# 22-1G_SFP.net
KiCad netlist of a schematic drawn in Altium Designer
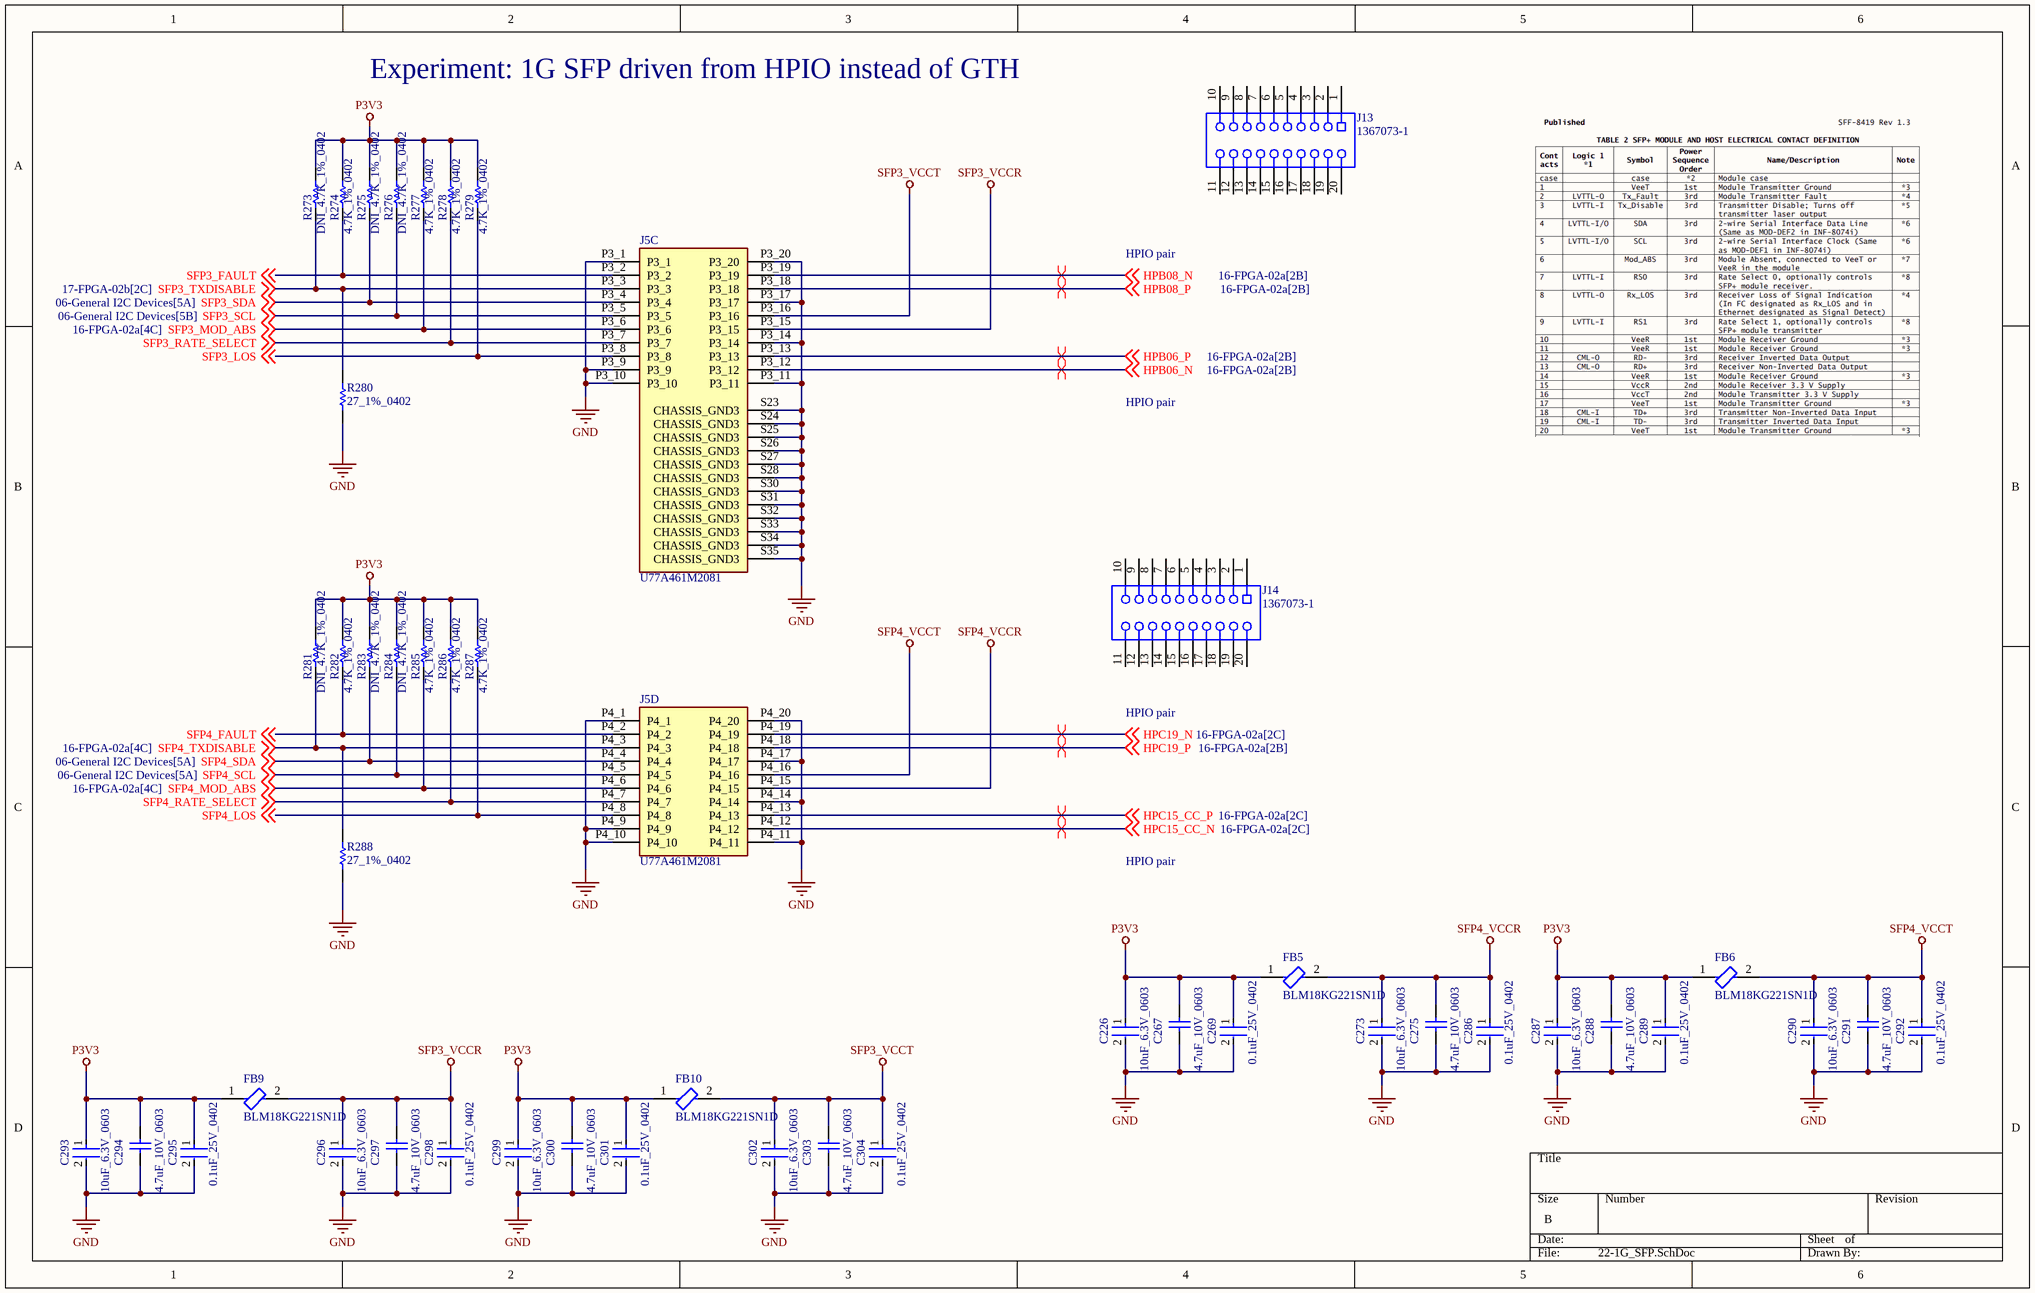
[diagram p0: 22-1G_SFP.SchDoc]

(export (version "E")
  (design (tool "Eeschema 10.0.6"))
  (components
    (comp (ref "C226")
      (value "10uF_6.3V_0603")
      (footprint "FP-C0603C106M9PACTU-MFG")
      (description "CAP CER 10UF 6.3V X5R 0603")
      (fields
        (field (name "MANUFACTURER PART NUMBER") "C0603C106M9PACTU")
        (field (name "MANUFACTURER") "Kemet")
      )
      (libsource (lib "Altium Content Vault") (part "b4654b650e69147ec39a6b967a45e02"))
    )
    (comp (ref "C267")
      (value "4.7uF_10V_0603")
      (footprint "CAPC1608X87X35NL15T15")
      (fields (field (name "PART NUMBER") "C0603C475K8PACTU") (field (name "MANUFACTURER") "Kemet"))
      (libsource (lib "Altium Content Vault") (part "CAP"))
    )
    (comp (ref "C269")
      (value "0.1uF_25V_0402")
      (footprint "FP-0402-L_1_0_1-W_0_5_0_1-IPC_C")
      (description "General Purpose Ceramic Capacitor, 0402, 100nF, 10%, X7R, 15%, 25V")
      (fields (field (name "VOLTAGE") "25V") (field (name "TOLERANCE") "10%"))
      (libsource (lib "Altium Content Vault") (part "b4654b650e69147ec39a6b967a45e02"))
    )
    (comp (ref "C273")
      (value "10uF_6.3V_0603")
      (footprint "FP-C0603C106M9PACTU-MFG")
      (description "CAP CER 10UF 6.3V X5R 0603")
      (fields
        (field (name "MANUFACTURER PART NUMBER") "C0603C106M9PACTU")
        (field (name "MANUFACTURER") "Kemet")
      )
      (libsource (lib "Altium Content Vault") (part "b4654b650e69147ec39a6b967a45e02"))
    )
    (comp (ref "C275")
      (value "4.7uF_10V_0603")
      (footprint "CAPC1608X87X35NL15T15")
      (fields (field (name "PART NUMBER") "C0603C475K8PACTU") (field (name "MANUFACTURER") "Kemet"))
      (libsource (lib "Altium Content Vault") (part "CAP"))
    )
    (comp (ref "C286")
      (value "0.1uF_25V_0402")
      (footprint "FP-0402-L_1_0_1-W_0_5_0_1-IPC_C")
      (description "General Purpose Ceramic Capacitor, 0402, 100nF, 10%, X7R, 15%, 25V")
      (fields (field (name "VOLTAGE") "25V") (field (name "TOLERANCE") "10%"))
      (libsource (lib "Altium Content Vault") (part "b4654b650e69147ec39a6b967a45e02"))
    )
    (comp (ref "C287")
      (value "10uF_6.3V_0603")
      (footprint "FP-C0603C106M9PACTU-MFG")
      (description "CAP CER 10UF 6.3V X5R 0603")
      (fields
        (field (name "MANUFACTURER PART NUMBER") "C0603C106M9PACTU")
        (field (name "MANUFACTURER") "Kemet")
      )
      (libsource (lib "Altium Content Vault") (part "b4654b650e69147ec39a6b967a45e02"))
    )
    (comp (ref "C288")
      (value "4.7uF_10V_0603")
      (footprint "CAPC1608X87X35NL15T15")
      (fields (field (name "PART NUMBER") "C0603C475K8PACTU") (field (name "MANUFACTURER") "Kemet"))
      (libsource (lib "Altium Content Vault") (part "CAP"))
    )
    (comp (ref "C289")
      (value "0.1uF_25V_0402")
      (footprint "FP-0402-L_1_0_1-W_0_5_0_1-IPC_C")
      (description "General Purpose Ceramic Capacitor, 0402, 100nF, 10%, X7R, 15%, 25V")
      (fields (field (name "VOLTAGE") "25V") (field (name "TOLERANCE") "10%"))
      (libsource (lib "Altium Content Vault") (part "b4654b650e69147ec39a6b967a45e02"))
    )
    (comp (ref "C290")
      (value "10uF_6.3V_0603")
      (footprint "FP-C0603C106M9PACTU-MFG")
      (description "CAP CER 10UF 6.3V X5R 0603")
      (fields
        (field (name "MANUFACTURER PART NUMBER") "C0603C106M9PACTU")
        (field (name "MANUFACTURER") "Kemet")
      )
      (libsource (lib "Altium Content Vault") (part "b4654b650e69147ec39a6b967a45e02"))
    )
    (comp (ref "C291")
      (value "4.7uF_10V_0603")
      (footprint "CAPC1608X87X35NL15T15")
      (fields (field (name "PART NUMBER") "C0603C475K8PACTU") (field (name "MANUFACTURER") "Kemet"))
      (libsource (lib "Altium Content Vault") (part "CAP"))
    )
    (comp (ref "C292")
      (value "0.1uF_25V_0402")
      (footprint "FP-0402-L_1_0_1-W_0_5_0_1-IPC_C")
      (description "General Purpose Ceramic Capacitor, 0402, 100nF, 10%, X7R, 15%, 25V")
      (fields (field (name "VOLTAGE") "25V") (field (name "TOLERANCE") "10%"))
      (libsource (lib "Altium Content Vault") (part "b4654b650e69147ec39a6b967a45e02"))
    )
    (comp (ref "C293")
      (value "10uF_6.3V_0603")
      (footprint "FP-C0603C106M9PACTU-MFG")
      (description "CAP CER 10UF 6.3V X5R 0603")
      (fields
        (field (name "MANUFACTURER PART NUMBER") "C0603C106M9PACTU")
        (field (name "MANUFACTURER") "Kemet")
      )
      (libsource (lib "Altium Content Vault") (part "b4654b650e69147ec39a6b967a45e02"))
    )
    (comp (ref "C294")
      (value "4.7uF_10V_0603")
      (footprint "CAPC1608X87X35NL15T15")
      (fields (field (name "PART NUMBER") "C0603C475K8PACTU") (field (name "MANUFACTURER") "Kemet"))
      (libsource (lib "Altium Content Vault") (part "CAP"))
    )
    (comp (ref "C295")
      (value "0.1uF_25V_0402")
      (footprint "FP-0402-L_1_0_1-W_0_5_0_1-IPC_C")
      (description "General Purpose Ceramic Capacitor, 0402, 100nF, 10%, X7R, 15%, 25V")
      (fields (field (name "VOLTAGE") "25V") (field (name "TOLERANCE") "10%"))
      (libsource (lib "Altium Content Vault") (part "b4654b650e69147ec39a6b967a45e02"))
    )
    (comp (ref "C296")
      (value "10uF_6.3V_0603")
      (footprint "FP-C0603C106M9PACTU-MFG")
      (description "CAP CER 10UF 6.3V X5R 0603")
      (fields
        (field (name "MANUFACTURER PART NUMBER") "C0603C106M9PACTU")
        (field (name "MANUFACTURER") "Kemet")
      )
      (libsource (lib "Altium Content Vault") (part "b4654b650e69147ec39a6b967a45e02"))
    )
    (comp (ref "C297")
      (value "4.7uF_10V_0603")
      (footprint "CAPC1608X87X35NL15T15")
      (fields (field (name "PART NUMBER") "C0603C475K8PACTU") (field (name "MANUFACTURER") "Kemet"))
      (libsource (lib "Altium Content Vault") (part "CAP"))
    )
    (comp (ref "C298")
      (value "0.1uF_25V_0402")
      (footprint "FP-0402-L_1_0_1-W_0_5_0_1-IPC_C")
      (description "General Purpose Ceramic Capacitor, 0402, 100nF, 10%, X7R, 15%, 25V")
      (fields (field (name "VOLTAGE") "25V") (field (name "TOLERANCE") "10%"))
      (libsource (lib "Altium Content Vault") (part "b4654b650e69147ec39a6b967a45e02"))
    )
    (comp (ref "C299")
      (value "10uF_6.3V_0603")
      (footprint "FP-C0603C106M9PACTU-MFG")
      (description "CAP CER 10UF 6.3V X5R 0603")
      (fields
        (field (name "MANUFACTURER PART NUMBER") "C0603C106M9PACTU")
        (field (name "MANUFACTURER") "Kemet")
      )
      (libsource (lib "Altium Content Vault") (part "b4654b650e69147ec39a6b967a45e02"))
    )
    (comp (ref "C300")
      (value "4.7uF_10V_0603")
      (footprint "CAPC1608X87X35NL15T15")
      (fields (field (name "PART NUMBER") "C0603C475K8PACTU") (field (name "MANUFACTURER") "Kemet"))
      (libsource (lib "Altium Content Vault") (part "CAP"))
    )
    (comp (ref "C301")
      (value "0.1uF_25V_0402")
      (footprint "FP-0402-L_1_0_1-W_0_5_0_1-IPC_C")
      (description "General Purpose Ceramic Capacitor, 0402, 100nF, 10%, X7R, 15%, 25V")
      (fields (field (name "VOLTAGE") "25V") (field (name "TOLERANCE") "10%"))
      (libsource (lib "Altium Content Vault") (part "b4654b650e69147ec39a6b967a45e02"))
    )
    (comp (ref "C302")
      (value "10uF_6.3V_0603")
      (footprint "FP-C0603C106M9PACTU-MFG")
      (description "CAP CER 10UF 6.3V X5R 0603")
      (fields
        (field (name "MANUFACTURER PART NUMBER") "C0603C106M9PACTU")
        (field (name "MANUFACTURER") "Kemet")
      )
      (libsource (lib "Altium Content Vault") (part "b4654b650e69147ec39a6b967a45e02"))
    )
    (comp (ref "C303")
      (value "4.7uF_10V_0603")
      (footprint "CAPC1608X87X35NL15T15")
      (fields (field (name "PART NUMBER") "C0603C475K8PACTU") (field (name "MANUFACTURER") "Kemet"))
      (libsource (lib "Altium Content Vault") (part "CAP"))
    )
    (comp (ref "C304")
      (value "0.1uF_25V_0402")
      (footprint "FP-0402-L_1_0_1-W_0_5_0_1-IPC_C")
      (description "General Purpose Ceramic Capacitor, 0402, 100nF, 10%, X7R, 15%, 25V")
      (fields (field (name "VOLTAGE") "25V") (field (name "TOLERANCE") "10%"))
      (libsource (lib "Altium Content Vault") (part "b4654b650e69147ec39a6b967a45e02"))
    )
    (comp (ref "FB5")
      (value "BLM18KG221SN1D")
      (footprint "FP-BLM18-0_15-t0_8-IPC_B")
      (description "Chip Ferrite Bead, 0603, 220Ω @ 100MHz, 0.05Ω, 25%, 2.2A")
      (fields (field (name "TOLERANCE") "25%"))
      (libsource (lib "Altium Content Vault") (part "5f30dd21d616792df468990f7003faa"))
    )
    (comp (ref "FB6")
      (value "BLM18KG221SN1D")
      (footprint "FP-BLM18-0_15-t0_8-IPC_B")
      (description "Chip Ferrite Bead, 0603, 220Ω @ 100MHz, 0.05Ω, 25%, 2.2A")
      (fields (field (name "TOLERANCE") "25%"))
      (libsource (lib "Altium Content Vault") (part "5f30dd21d616792df468990f7003faa"))
    )
    (comp (ref "FB9")
      (value "BLM18KG221SN1D")
      (footprint "FP-BLM18-0_15-t0_8-IPC_B")
      (description "Chip Ferrite Bead, 0603, 220Ω @ 100MHz, 0.05Ω, 25%, 2.2A")
      (fields (field (name "TOLERANCE") "25%"))
      (libsource (lib "Altium Content Vault") (part "5f30dd21d616792df468990f7003faa"))
    )
    (comp (ref "FB10")
      (value "BLM18KG221SN1D")
      (footprint "FP-BLM18-0_15-t0_8-IPC_B")
      (description "Chip Ferrite Bead, 0603, 220Ω @ 100MHz, 0.05Ω, 25%, 2.2A")
      (fields (field (name "TOLERANCE") "25%"))
      (libsource (lib "Altium Content Vault") (part "5f30dd21d616792df468990f7003faa"))
    )
    (comp (ref "J5")
      (value "U77A461M2081")
      (footprint "AMPHENOL_U77A461M2081")
      (fields (field (name "MF") "AMPHENOL ICC / FCI"))
      (libsource (lib "U77A461M2081") (part "U77A461M2081"))
    )
    (comp (ref "J13")
      (value "1367073-1")
      (footprint "TECO-1367073-1_V")
      (fields (field (name "MANUFACTURER") "TE Connectivity"))
      (libsource (lib "Altium Content Vault") (part "CN-2P-F-R20_B"))
    )
    (comp (ref "J14")
      (value "1367073-1")
      (footprint "TECO-1367073-1_V")
      (fields (field (name "MANUFACTURER") "TE Connectivity"))
      (libsource (lib "Altium Content Vault") (part "CN-2P-F-R20_B"))
    )
    (comp (ref "R273")
      (value "DNI_4.7K_1%_0402")
      (footprint "RESC1005X40X25NL10T10")
      (fields (field (name "MANUFACTURER") "Bourns") (field (name "PART NUMBER") "CR0402-FX-4701GLF"))
      (libsource (lib "Altium Content Vault") (part "RES"))
    )
    (comp (ref "R274")
      (value "4.7K_1%_0402")
      (footprint "RESC1005X40X25NL10T10")
      (fields (field (name "MANUFACTURER") "Bourns") (field (name "PART NUMBER") "CR0402-FX-4701GLF"))
      (libsource (lib "Altium Content Vault") (part "RES"))
    )
    (comp (ref "R275")
      (value "DNI_4.7K_1%_0402")
      (footprint "RESC1005X40X25NL10T10")
      (fields (field (name "MANUFACTURER") "Bourns") (field (name "PART NUMBER") "CR0402-FX-4701GLF"))
      (libsource (lib "Altium Content Vault") (part "RES"))
    )
    (comp (ref "R276")
      (value "DNI_4.7K_1%_0402")
      (footprint "RESC1005X40X25NL10T10")
      (fields (field (name "MANUFACTURER") "Bourns") (field (name "PART NUMBER") "CR0402-FX-4701GLF"))
      (libsource (lib "Altium Content Vault") (part "RES"))
    )
    (comp (ref "R277")
      (value "4.7K_1%_0402")
      (footprint "RESC1005X40X25NL10T10")
      (fields (field (name "MANUFACTURER") "Bourns") (field (name "PART NUMBER") "CR0402-FX-4701GLF"))
      (libsource (lib "Altium Content Vault") (part "RES"))
    )
    (comp (ref "R278")
      (value "4.7K_1%_0402")
      (footprint "RESC1005X40X25NL10T10")
      (fields (field (name "MANUFACTURER") "Bourns") (field (name "PART NUMBER") "CR0402-FX-4701GLF"))
      (libsource (lib "Altium Content Vault") (part "RES"))
    )
    (comp (ref "R279")
      (value "4.7K_1%_0402")
      (footprint "RESC1005X40X25NL10T10")
      (fields (field (name "MANUFACTURER") "Bourns") (field (name "PART NUMBER") "CR0402-FX-4701GLF"))
      (libsource (lib "Altium Content Vault") (part "RES"))
    )
    (comp (ref "R280")
      (value "27_1%_0402")
      (footprint "RESC1005X40X25NL05T05")
      (fields (field (name "PART NUMBER") "CRCW040227R0FKED") (field (name "MANUFACTURER") "Vishay Dale"))
      (libsource (lib "Altium Content Vault") (part "RES"))
    )
    (comp (ref "R281")
      (value "DNI_4.7K_1%_0402")
      (footprint "RESC1005X40X25NL10T10")
      (fields (field (name "MANUFACTURER") "Bourns") (field (name "PART NUMBER") "CR0402-FX-4701GLF"))
      (libsource (lib "Altium Content Vault") (part "RES"))
    )
    (comp (ref "R282")
      (value "4.7K_1%_0402")
      (footprint "RESC1005X40X25NL10T10")
      (fields (field (name "MANUFACTURER") "Bourns") (field (name "PART NUMBER") "CR0402-FX-4701GLF"))
      (libsource (lib "Altium Content Vault") (part "RES"))
    )
    (comp (ref "R283")
      (value "DNI_4.7K_1%_0402")
      (footprint "RESC1005X40X25NL10T10")
      (fields (field (name "MANUFACTURER") "Bourns") (field (name "PART NUMBER") "CR0402-FX-4701GLF"))
      (libsource (lib "Altium Content Vault") (part "RES"))
    )
    (comp (ref "R284")
      (value "DNI_4.7K_1%_0402")
      (footprint "RESC1005X40X25NL10T10")
      (fields (field (name "MANUFACTURER") "Bourns") (field (name "PART NUMBER") "CR0402-FX-4701GLF"))
      (libsource (lib "Altium Content Vault") (part "RES"))
    )
    (comp (ref "R285")
      (value "4.7K_1%_0402")
      (footprint "RESC1005X40X25NL10T10")
      (fields (field (name "MANUFACTURER") "Bourns") (field (name "PART NUMBER") "CR0402-FX-4701GLF"))
      (libsource (lib "Altium Content Vault") (part "RES"))
    )
    (comp (ref "R286")
      (value "4.7K_1%_0402")
      (footprint "RESC1005X40X25NL10T10")
      (fields (field (name "MANUFACTURER") "Bourns") (field (name "PART NUMBER") "CR0402-FX-4701GLF"))
      (libsource (lib "Altium Content Vault") (part "RES"))
    )
    (comp (ref "R287")
      (value "4.7K_1%_0402")
      (footprint "RESC1005X40X25NL10T10")
      (fields (field (name "MANUFACTURER") "Bourns") (field (name "PART NUMBER") "CR0402-FX-4701GLF"))
      (libsource (lib "Altium Content Vault") (part "RES"))
    )
    (comp (ref "R288")
      (value "27_1%_0402")
      (footprint "RESC1005X40X25NL05T05")
      (fields (field (name "PART NUMBER") "CRCW040227R0FKED") (field (name "MANUFACTURER") "Vishay Dale"))
      (libsource (lib "Altium Content Vault") (part "RES"))
    )
  )
  (nets
    (net (code "1") (name "GND") (class "Default")
      (node (ref "C226") (pin "2") (pinfunction "2_2") (pintype "passive"))
      (node (ref "C267") (pin "1") (pinfunction "1_1") (pintype "passive"))
      (node (ref "C269") (pin "2") (pinfunction "2_2") (pintype "passive"))
      (node (ref "C273") (pin "2") (pinfunction "2_2") (pintype "passive"))
      (node (ref "C275") (pin "1") (pinfunction "1_1") (pintype "passive"))
      (node (ref "C286") (pin "2") (pinfunction "2_2") (pintype "passive"))
      (node (ref "C287") (pin "2") (pinfunction "2_2") (pintype "passive"))
      (node (ref "C288") (pin "1") (pinfunction "1_1") (pintype "passive"))
      (node (ref "C289") (pin "2") (pinfunction "2_2") (pintype "passive"))
      (node (ref "C290") (pin "2") (pinfunction "2_2") (pintype "passive"))
      (node (ref "C291") (pin "1") (pinfunction "1_1") (pintype "passive"))
      (node (ref "C292") (pin "2") (pinfunction "2_2") (pintype "passive"))
      (node (ref "C293") (pin "2") (pinfunction "2_2") (pintype "passive"))
      (node (ref "C294") (pin "1") (pinfunction "1_1") (pintype "passive"))
      (node (ref "C295") (pin "2") (pinfunction "2_2") (pintype "passive"))
      (node (ref "C296") (pin "2") (pinfunction "2_2") (pintype "passive"))
      (node (ref "C297") (pin "1") (pinfunction "1_1") (pintype "passive"))
      (node (ref "C298") (pin "2") (pinfunction "2_2") (pintype "passive"))
      (node (ref "C299") (pin "2") (pinfunction "2_2") (pintype "passive"))
      (node (ref "C300") (pin "1") (pinfunction "1_1") (pintype "passive"))
      (node (ref "C301") (pin "2") (pinfunction "2_2") (pintype "passive"))
      (node (ref "C302") (pin "2") (pinfunction "2_2") (pintype "passive"))
      (node (ref "C303") (pin "1") (pinfunction "1_1") (pintype "passive"))
      (node (ref "C304") (pin "2") (pinfunction "2_2") (pintype "passive"))
      (node (ref "J5") (pin "P3_1") (pinfunction "P3_1_P3_1") (pintype "passive"))
      (node (ref "J5") (pin "P3_10") (pinfunction "P3_10_P3_10") (pintype "passive"))
      (node (ref "J5") (pin "P3_11") (pinfunction "P3_11_P3_11") (pintype "passive"))
      (node (ref "J5") (pin "P3_14") (pinfunction "P3_14_P3_14") (pintype "passive"))
      (node (ref "J5") (pin "P3_17") (pinfunction "P3_17_P3_17") (pintype "passive"))
      (node (ref "J5") (pin "P3_20") (pinfunction "P3_20_P3_20") (pintype "passive"))
      (node (ref "J5") (pin "P3_9") (pinfunction "P3_9_P3_9") (pintype "passive"))
      (node (ref "J5") (pin "P4_1") (pinfunction "P4_1_P4_1") (pintype "passive"))
      (node (ref "J5") (pin "P4_10") (pinfunction "P4_10_P4_10") (pintype "passive"))
      (node (ref "J5") (pin "P4_11") (pinfunction "P4_11_P4_11") (pintype "passive"))
      (node (ref "J5") (pin "P4_14") (pinfunction "P4_14_P4_14") (pintype "passive"))
      (node (ref "J5") (pin "P4_17") (pinfunction "P4_17_P4_17") (pintype "passive"))
      (node (ref "J5") (pin "P4_20") (pinfunction "P4_20_P4_20") (pintype "passive"))
      (node (ref "J5") (pin "P4_9") (pinfunction "P4_9_P4_9") (pintype "passive"))
      (node (ref "J5") (pin "S23") (pinfunction "CHASSIS_GND3_S23") (pintype "passive"))
      (node (ref "J5") (pin "S24") (pinfunction "CHASSIS_GND3_S24") (pintype "passive"))
      (node (ref "J5") (pin "S25") (pinfunction "CHASSIS_GND3_S25") (pintype "passive"))
      (node (ref "J5") (pin "S26") (pinfunction "CHASSIS_GND3_S26") (pintype "passive"))
      (node (ref "J5") (pin "S27") (pinfunction "CHASSIS_GND3_S27") (pintype "passive"))
      (node (ref "J5") (pin "S28") (pinfunction "CHASSIS_GND3_S28") (pintype "passive"))
      (node (ref "J5") (pin "S30") (pinfunction "CHASSIS_GND3_S30") (pintype "passive"))
      (node (ref "J5") (pin "S31") (pinfunction "CHASSIS_GND3_S31") (pintype "passive"))
      (node (ref "J5") (pin "S32") (pinfunction "CHASSIS_GND3_S32") (pintype "passive"))
      (node (ref "J5") (pin "S33") (pinfunction "CHASSIS_GND3_S33") (pintype "passive"))
      (node (ref "J5") (pin "S34") (pinfunction "CHASSIS_GND3_S34") (pintype "passive"))
      (node (ref "J5") (pin "S35") (pinfunction "CHASSIS_GND3_S35") (pintype "passive"))
      (node (ref "R280") (pin "1") (pinfunction "1_1") (pintype "passive"))
      (node (ref "R288") (pin "1") (pinfunction "1_1") (pintype "passive"))
    )
    (net (code "2") (name "HPB06_N") (class "Default")
      (node (ref "J5") (pin "P3_12") (pinfunction "P3_12_P3_12") (pintype "passive"))
    )
    (net (code "3") (name "HPB06_P") (class "Default")
      (node (ref "J5") (pin "P3_13") (pinfunction "P3_13_P3_13") (pintype "passive"))
    )
    (net (code "4") (name "HPB08_N") (class "Default")
      (node (ref "J5") (pin "P3_19") (pinfunction "P3_19_P3_19") (pintype "passive"))
    )
    (net (code "5") (name "HPB08_P") (class "Default")
      (node (ref "J5") (pin "P3_18") (pinfunction "P3_18_P3_18") (pintype "passive"))
    )
    (net (code "6") (name "HPC15_CC_N") (class "Default")
      (node (ref "J5") (pin "P4_12") (pinfunction "P4_12_P4_12") (pintype "passive"))
    )
    (net (code "7") (name "HPC15_CC_P") (class "Default")
      (node (ref "J5") (pin "P4_13") (pinfunction "P4_13_P4_13") (pintype "passive"))
    )
    (net (code "8") (name "HPC19_N") (class "Default")
      (node (ref "J5") (pin "P4_19") (pinfunction "P4_19_P4_19") (pintype "passive"))
    )
    (net (code "9") (name "HPC19_P") (class "Default")
      (node (ref "J5") (pin "P4_18") (pinfunction "P4_18_P4_18") (pintype "passive"))
    )
    (net (code "10") (name "P3V3") (class "Default")
      (node (ref "C226") (pin "1") (pinfunction "1_1") (pintype "passive"))
      (node (ref "C267") (pin "2") (pinfunction "2_2") (pintype "passive"))
      (node (ref "C269") (pin "1") (pinfunction "1_1") (pintype "passive"))
      (node (ref "C287") (pin "1") (pinfunction "1_1") (pintype "passive"))
      (node (ref "C288") (pin "2") (pinfunction "2_2") (pintype "passive"))
      (node (ref "C289") (pin "1") (pinfunction "1_1") (pintype "passive"))
      (node (ref "C293") (pin "1") (pinfunction "1_1") (pintype "passive"))
      (node (ref "C294") (pin "2") (pinfunction "2_2") (pintype "passive"))
      (node (ref "C295") (pin "1") (pinfunction "1_1") (pintype "passive"))
      (node (ref "C299") (pin "1") (pinfunction "1_1") (pintype "passive"))
      (node (ref "C300") (pin "2") (pinfunction "2_2") (pintype "passive"))
      (node (ref "C301") (pin "1") (pinfunction "1_1") (pintype "passive"))
      (node (ref "FB10") (pin "1") (pinfunction "1_1") (pintype "passive"))
      (node (ref "FB5") (pin "1") (pinfunction "1_1") (pintype "passive"))
      (node (ref "FB6") (pin "1") (pinfunction "1_1") (pintype "passive"))
      (node (ref "FB9") (pin "1") (pinfunction "1_1") (pintype "passive"))
      (node (ref "R273") (pin "1") (pinfunction "1_1") (pintype "passive"))
      (node (ref "R274") (pin "1") (pinfunction "1_1") (pintype "passive"))
      (node (ref "R275") (pin "1") (pinfunction "1_1") (pintype "passive"))
      (node (ref "R276") (pin "1") (pinfunction "1_1") (pintype "passive"))
      (node (ref "R277") (pin "1") (pinfunction "1_1") (pintype "passive"))
      (node (ref "R278") (pin "1") (pinfunction "1_1") (pintype "passive"))
      (node (ref "R279") (pin "1") (pinfunction "1_1") (pintype "passive"))
      (node (ref "R281") (pin "1") (pinfunction "1_1") (pintype "passive"))
      (node (ref "R282") (pin "1") (pinfunction "1_1") (pintype "passive"))
      (node (ref "R283") (pin "1") (pinfunction "1_1") (pintype "passive"))
      (node (ref "R284") (pin "1") (pinfunction "1_1") (pintype "passive"))
      (node (ref "R285") (pin "1") (pinfunction "1_1") (pintype "passive"))
      (node (ref "R286") (pin "1") (pinfunction "1_1") (pintype "passive"))
      (node (ref "R287") (pin "1") (pinfunction "1_1") (pintype "passive"))
    )
    (net (code "11") (name "SFP3_FAULT") (class "Default")
      (node (ref "J5") (pin "P3_2") (pinfunction "P3_2_P3_2") (pintype "passive"))
      (node (ref "R274") (pin "2") (pinfunction "2_2") (pintype "passive"))
    )
    (net (code "12") (name "SFP3_LOS") (class "Default")
      (node (ref "J5") (pin "P3_8") (pinfunction "P3_8_P3_8") (pintype "passive"))
      (node (ref "R279") (pin "2") (pinfunction "2_2") (pintype "passive"))
    )
    (net (code "13") (name "SFP3_MOD_ABS") (class "Default")
      (node (ref "J5") (pin "P3_6") (pinfunction "P3_6_P3_6") (pintype "passive"))
      (node (ref "R277") (pin "2") (pinfunction "2_2") (pintype "passive"))
    )
    (net (code "14") (name "SFP3_RATE_SELECT") (class "Default")
      (node (ref "J5") (pin "P3_7") (pinfunction "P3_7_P3_7") (pintype "passive"))
      (node (ref "R278") (pin "2") (pinfunction "2_2") (pintype "passive"))
    )
    (net (code "15") (name "SFP3_SCL") (class "Default")
      (node (ref "J5") (pin "P3_5") (pinfunction "P3_5_P3_5") (pintype "passive"))
      (node (ref "R276") (pin "2") (pinfunction "2_2") (pintype "passive"))
    )
    (net (code "16") (name "SFP3_SDA") (class "Default")
      (node (ref "J5") (pin "P3_4") (pinfunction "P3_4_P3_4") (pintype "passive"))
      (node (ref "R275") (pin "2") (pinfunction "2_2") (pintype "passive"))
    )
    (net (code "17") (name "SFP3_TXDISABLE") (class "Default")
      (node (ref "J5") (pin "P3_3") (pinfunction "P3_3_P3_3") (pintype "passive"))
      (node (ref "R273") (pin "2") (pinfunction "2_2") (pintype "passive"))
      (node (ref "R280") (pin "2") (pinfunction "2_2") (pintype "passive"))
    )
    (net (code "18") (name "SFP3_VCCR") (class "Default")
      (node (ref "C296") (pin "1") (pinfunction "1_1") (pintype "passive"))
      (node (ref "C297") (pin "2") (pinfunction "2_2") (pintype "passive"))
      (node (ref "C298") (pin "1") (pinfunction "1_1") (pintype "passive"))
      (node (ref "FB9") (pin "2") (pinfunction "2_2") (pintype "passive"))
      (node (ref "J5") (pin "P3_15") (pinfunction "P3_15_P3_15") (pintype "passive"))
    )
    (net (code "19") (name "SFP3_VCCT") (class "Default")
      (node (ref "C302") (pin "1") (pinfunction "1_1") (pintype "passive"))
      (node (ref "C303") (pin "2") (pinfunction "2_2") (pintype "passive"))
      (node (ref "C304") (pin "1") (pinfunction "1_1") (pintype "passive"))
      (node (ref "FB10") (pin "2") (pinfunction "2_2") (pintype "passive"))
      (node (ref "J5") (pin "P3_16") (pinfunction "P3_16_P3_16") (pintype "passive"))
    )
    (net (code "20") (name "SFP4_FAULT") (class "Default")
      (node (ref "J5") (pin "P4_2") (pinfunction "P4_2_P4_2") (pintype "passive"))
      (node (ref "R282") (pin "2") (pinfunction "2_2") (pintype "passive"))
    )
    (net (code "21") (name "SFP4_LOS") (class "Default")
      (node (ref "J5") (pin "P4_8") (pinfunction "P4_8_P4_8") (pintype "passive"))
      (node (ref "R287") (pin "2") (pinfunction "2_2") (pintype "passive"))
    )
    (net (code "22") (name "SFP4_MOD_ABS") (class "Default")
      (node (ref "J5") (pin "P4_6") (pinfunction "P4_6_P4_6") (pintype "passive"))
      (node (ref "R285") (pin "2") (pinfunction "2_2") (pintype "passive"))
    )
    (net (code "23") (name "SFP4_RATE_SELECT") (class "Default")
      (node (ref "J5") (pin "P4_7") (pinfunction "P4_7_P4_7") (pintype "passive"))
      (node (ref "R286") (pin "2") (pinfunction "2_2") (pintype "passive"))
    )
    (net (code "24") (name "SFP4_SCL") (class "Default")
      (node (ref "J5") (pin "P4_5") (pinfunction "P4_5_P4_5") (pintype "passive"))
      (node (ref "R284") (pin "2") (pinfunction "2_2") (pintype "passive"))
    )
    (net (code "25") (name "SFP4_SDA") (class "Default")
      (node (ref "J5") (pin "P4_4") (pinfunction "P4_4_P4_4") (pintype "passive"))
      (node (ref "R283") (pin "2") (pinfunction "2_2") (pintype "passive"))
    )
    (net (code "26") (name "SFP4_TXDISABLE") (class "Default")
      (node (ref "J5") (pin "P4_3") (pinfunction "P4_3_P4_3") (pintype "passive"))
      (node (ref "R281") (pin "2") (pinfunction "2_2") (pintype "passive"))
      (node (ref "R288") (pin "2") (pinfunction "2_2") (pintype "passive"))
    )
    (net (code "27") (name "SFP4_VCCR") (class "Default")
      (node (ref "C273") (pin "1") (pinfunction "1_1") (pintype "passive"))
      (node (ref "C275") (pin "2") (pinfunction "2_2") (pintype "passive"))
      (node (ref "C286") (pin "1") (pinfunction "1_1") (pintype "passive"))
      (node (ref "FB5") (pin "2") (pinfunction "2_2") (pintype "passive"))
      (node (ref "J5") (pin "P4_15") (pinfunction "P4_15_P4_15") (pintype "passive"))
    )
    (net (code "28") (name "SFP4_VCCT") (class "Default")
      (node (ref "C290") (pin "1") (pinfunction "1_1") (pintype "passive"))
      (node (ref "C291") (pin "2") (pinfunction "2_2") (pintype "passive"))
      (node (ref "C292") (pin "1") (pinfunction "1_1") (pintype "passive"))
      (node (ref "FB6") (pin "2") (pinfunction "2_2") (pintype "passive"))
      (node (ref "J5") (pin "P4_16") (pinfunction "P4_16_P4_16") (pintype "passive"))
    )
    (net (code "29") (name "unconnected-(J13-Pad1)") (class "Default")
      (node (ref "J13") (pin "1") (pinfunction "1_1") (pintype "passive"))
    )
    (net (code "30") (name "unconnected-(J13-Pad2)") (class "Default")
      (node (ref "J13") (pin "2") (pinfunction "2_2") (pintype "passive"))
    )
    (net (code "31") (name "unconnected-(J13-Pad3)") (class "Default")
      (node (ref "J13") (pin "3") (pinfunction "3_3") (pintype "passive"))
    )
    (net (code "32") (name "unconnected-(J13-Pad4)") (class "Default")
      (node (ref "J13") (pin "4") (pinfunction "4_4") (pintype "passive"))
    )
    (net (code "33") (name "unconnected-(J13-Pad5)") (class "Default")
      (node (ref "J13") (pin "5") (pinfunction "5_5") (pintype "passive"))
    )
    (net (code "34") (name "unconnected-(J13-Pad6)") (class "Default")
      (node (ref "J13") (pin "6") (pinfunction "6_6") (pintype "passive"))
    )
    (net (code "35") (name "unconnected-(J13-Pad7)") (class "Default")
      (node (ref "J13") (pin "7") (pinfunction "7_7") (pintype "passive"))
    )
    (net (code "36") (name "unconnected-(J13-Pad8)") (class "Default")
      (node (ref "J13") (pin "8") (pinfunction "8_8") (pintype "passive"))
    )
    (net (code "37") (name "unconnected-(J13-Pad9)") (class "Default")
      (node (ref "J13") (pin "9") (pinfunction "9_9") (pintype "passive"))
    )
    (net (code "38") (name "unconnected-(J13-Pad10)") (class "Default")
      (node (ref "J13") (pin "10") (pinfunction "10_10") (pintype "passive"))
    )
    (net (code "39") (name "unconnected-(J13-Pad11)") (class "Default")
      (node (ref "J13") (pin "11") (pinfunction "11_11") (pintype "passive"))
    )
    (net (code "40") (name "unconnected-(J13-Pad12)") (class "Default")
      (node (ref "J13") (pin "12") (pinfunction "12_12") (pintype "passive"))
    )
    (net (code "41") (name "unconnected-(J13-Pad13)") (class "Default")
      (node (ref "J13") (pin "13") (pinfunction "13_13") (pintype "passive"))
    )
    (net (code "42") (name "unconnected-(J13-Pad14)") (class "Default")
      (node (ref "J13") (pin "14") (pinfunction "14_14") (pintype "passive"))
    )
    (net (code "43") (name "unconnected-(J13-Pad15)") (class "Default")
      (node (ref "J13") (pin "15") (pinfunction "15_15") (pintype "passive"))
    )
    (net (code "44") (name "unconnected-(J13-Pad16)") (class "Default")
      (node (ref "J13") (pin "16") (pinfunction "16_16") (pintype "passive"))
    )
    (net (code "45") (name "unconnected-(J13-Pad17)") (class "Default")
      (node (ref "J13") (pin "17") (pinfunction "17_17") (pintype "passive"))
    )
    (net (code "46") (name "unconnected-(J13-Pad18)") (class "Default")
      (node (ref "J13") (pin "18") (pinfunction "18_18") (pintype "passive"))
    )
    (net (code "47") (name "unconnected-(J13-Pad19)") (class "Default")
      (node (ref "J13") (pin "19") (pinfunction "19_19") (pintype "passive"))
    )
    (net (code "48") (name "unconnected-(J13-Pad20)") (class "Default")
      (node (ref "J13") (pin "20") (pinfunction "20_20") (pintype "passive"))
    )
    (net (code "49") (name "unconnected-(J14-Pad1)") (class "Default")
      (node (ref "J14") (pin "1") (pinfunction "1_1") (pintype "passive"))
    )
    (net (code "50") (name "unconnected-(J14-Pad2)") (class "Default")
      (node (ref "J14") (pin "2") (pinfunction "2_2") (pintype "passive"))
    )
    (net (code "51") (name "unconnected-(J14-Pad3)") (class "Default")
      (node (ref "J14") (pin "3") (pinfunction "3_3") (pintype "passive"))
    )
    (net (code "52") (name "unconnected-(J14-Pad4)") (class "Default")
      (node (ref "J14") (pin "4") (pinfunction "4_4") (pintype "passive"))
    )
    (net (code "53") (name "unconnected-(J14-Pad5)") (class "Default")
      (node (ref "J14") (pin "5") (pinfunction "5_5") (pintype "passive"))
    )
    (net (code "54") (name "unconnected-(J14-Pad6)") (class "Default")
      (node (ref "J14") (pin "6") (pinfunction "6_6") (pintype "passive"))
    )
    (net (code "55") (name "unconnected-(J14-Pad7)") (class "Default")
      (node (ref "J14") (pin "7") (pinfunction "7_7") (pintype "passive"))
    )
    (net (code "56") (name "unconnected-(J14-Pad8)") (class "Default")
      (node (ref "J14") (pin "8") (pinfunction "8_8") (pintype "passive"))
    )
    (net (code "57") (name "unconnected-(J14-Pad9)") (class "Default")
      (node (ref "J14") (pin "9") (pinfunction "9_9") (pintype "passive"))
    )
    (net (code "58") (name "unconnected-(J14-Pad10)") (class "Default")
      (node (ref "J14") (pin "10") (pinfunction "10_10") (pintype "passive"))
    )
    (net (code "59") (name "unconnected-(J14-Pad11)") (class "Default")
      (node (ref "J14") (pin "11") (pinfunction "11_11") (pintype "passive"))
    )
    (net (code "60") (name "unconnected-(J14-Pad12)") (class "Default")
      (node (ref "J14") (pin "12") (pinfunction "12_12") (pintype "passive"))
    )
    (net (code "61") (name "unconnected-(J14-Pad13)") (class "Default")
      (node (ref "J14") (pin "13") (pinfunction "13_13") (pintype "passive"))
    )
    (net (code "62") (name "unconnected-(J14-Pad14)") (class "Default")
      (node (ref "J14") (pin "14") (pinfunction "14_14") (pintype "passive"))
    )
    (net (code "63") (name "unconnected-(J14-Pad15)") (class "Default")
      (node (ref "J14") (pin "15") (pinfunction "15_15") (pintype "passive"))
    )
    (net (code "64") (name "unconnected-(J14-Pad16)") (class "Default")
      (node (ref "J14") (pin "16") (pinfunction "16_16") (pintype "passive"))
    )
    (net (code "65") (name "unconnected-(J14-Pad17)") (class "Default")
      (node (ref "J14") (pin "17") (pinfunction "17_17") (pintype "passive"))
    )
    (net (code "66") (name "unconnected-(J14-Pad18)") (class "Default")
      (node (ref "J14") (pin "18") (pinfunction "18_18") (pintype "passive"))
    )
    (net (code "67") (name "unconnected-(J14-Pad19)") (class "Default")
      (node (ref "J14") (pin "19") (pinfunction "19_19") (pintype "passive"))
    )
    (net (code "68") (name "unconnected-(J14-Pad20)") (class "Default")
      (node (ref "J14") (pin "20") (pinfunction "20_20") (pintype "passive"))
    )
  )
)
